# NET.net
KiCad netlist of a schematic drawn in Altium Designer
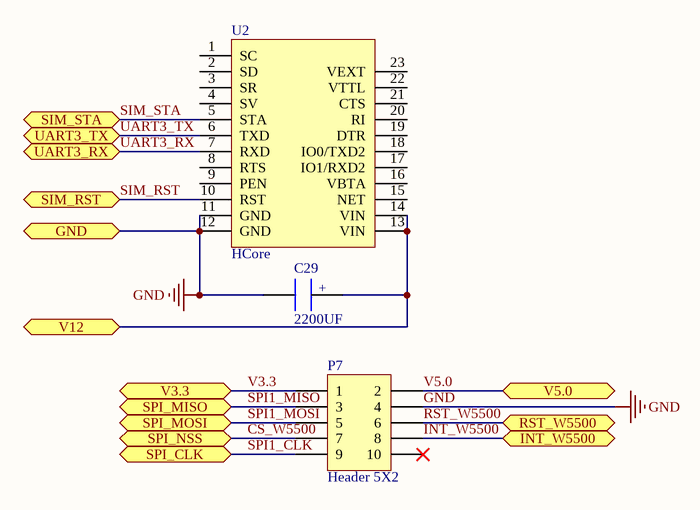
[diagram p0: NET.SchDoc]

(export (version "E")
  (design (tool "Eeschema 10.0.6"))
  (components
    (comp (ref "C29") (value "2200UF") (footprint "8X12_CAP") (libsource (lib "mylib") (part "CAP")))
    (comp (ref "P7")
      (value "Header 5X2")
      (footprint "HDR2X5")
      (description "Header, 5-Pin, Dual row")
      (fields (field (name "PUBLISHER") "Altium Limited"))
      (libsource (lib "Miscellaneous Connectors") (part "Header 5X2"))
    )
    (comp (ref "U2") (value "HCore") (footprint "HCore") (libsource (lib "mylib") (part "HCore")))
  )
  (nets
    (net (code "1") (name "/CS_W5500") (class "Default")
      (node (ref "P7") (pin "7") (pinfunction "7_7") (pintype "passive"))
    )
    (net (code "2") (name "/INT_W5500") (class "Default")
      (node (ref "P7") (pin "8") (pinfunction "8_8") (pintype "passive"))
    )
    (net (code "3") (name "/RST_W5500") (class "Default")
      (node (ref "P7") (pin "6") (pinfunction "6_6") (pintype "passive"))
    )
    (net (code "4") (name "/SIM_RST") (class "Default")
      (node (ref "U2") (pin "10") (pinfunction "RST_10") (pintype "passive"))
    )
    (net (code "5") (name "/SIM_STA") (class "Default")
      (node (ref "U2") (pin "5") (pinfunction "STA_5") (pintype "passive"))
    )
    (net (code "6") (name "/SPI1_CLK") (class "Default")
      (node (ref "P7") (pin "9") (pinfunction "9_9") (pintype "passive"))
    )
    (net (code "7") (name "/SPI1_MISO") (class "Default")
      (node (ref "P7") (pin "3") (pinfunction "3_3") (pintype "passive"))
    )
    (net (code "8") (name "/SPI1_MOSI") (class "Default")
      (node (ref "P7") (pin "5") (pinfunction "5_5") (pintype "passive"))
    )
    (net (code "9") (name "/UART3_RX") (class "Default")
      (node (ref "U2") (pin "7") (pinfunction "RXD_7") (pintype "passive"))
    )
    (net (code "10") (name "/UART3_TX") (class "Default")
      (node (ref "U2") (pin "6") (pinfunction "TXD_6") (pintype "passive"))
    )
    (net (code "11") (name "/V3.3") (class "Default")
      (node (ref "P7") (pin "1") (pinfunction "1_1") (pintype "passive"))
    )
    (net (code "12") (name "/V5.0") (class "Default")
      (node (ref "P7") (pin "2") (pinfunction "2_2") (pintype "passive"))
    )
    (net (code "13") (name "/V12") (class "Default")
      (node (ref "C29") (pin "1") (pinfunction "1_1") (pintype "passive"))
      (node (ref "U2") (pin "13") (pinfunction "VIN_13") (pintype "passive"))
      (node (ref "U2") (pin "14") (pinfunction "VIN_14") (pintype "passive"))
    )
    (net (code "14") (name "GND") (class "Default")
      (node (ref "C29") (pin "2") (pinfunction "2_2") (pintype "passive"))
      (node (ref "P7") (pin "4") (pinfunction "4_4") (pintype "passive"))
      (node (ref "U2") (pin "11") (pinfunction "GND_11") (pintype "passive"))
      (node (ref "U2") (pin "12") (pinfunction "GND_12") (pintype "passive"))
    )
    (net (code "15") (name "unconnected-(P7-Pad10)") (class "Default")
      (node (ref "P7") (pin "10") (pinfunction "10_10") (pintype "passive+no_connect"))
    )
    (net (code "16") (name "unconnected-(U2-CTS-Pad21)") (class "Default")
      (node (ref "U2") (pin "21") (pinfunction "CTS_21") (pintype "passive"))
    )
    (net (code "17") (name "unconnected-(U2-DTR-Pad19)") (class "Default")
      (node (ref "U2") (pin "19") (pinfunction "DTR_19") (pintype "passive"))
    )
    (net (code "18") (name "unconnected-(U2-IO0{slash}TXD2-Pad18)") (class "Default")
      (node (ref "U2") (pin "18") (pinfunction "IO0/TXD2_18") (pintype "passive"))
    )
    (net (code "19") (name "unconnected-(U2-IO1{slash}RXD2-Pad17)") (class "Default")
      (node (ref "U2") (pin "17") (pinfunction "IO1/RXD2_17") (pintype "passive"))
    )
    (net (code "20") (name "unconnected-(U2-NET-Pad15)") (class "Default")
      (node (ref "U2") (pin "15") (pinfunction "NET_15") (pintype "passive"))
    )
    (net (code "21") (name "unconnected-(U2-PEN-Pad9)") (class "Default")
      (node (ref "U2") (pin "9") (pinfunction "PEN_9") (pintype "passive"))
    )
    (net (code "22") (name "unconnected-(U2-RI-Pad20)") (class "Default")
      (node (ref "U2") (pin "20") (pinfunction "RI_20") (pintype "passive"))
    )
    (net (code "23") (name "unconnected-(U2-RTS-Pad8)") (class "Default")
      (node (ref "U2") (pin "8") (pinfunction "RTS_8") (pintype "passive"))
    )
    (net (code "24") (name "unconnected-(U2-SC-Pad1)") (class "Default")
      (node (ref "U2") (pin "1") (pinfunction "SC_1") (pintype "passive"))
    )
    (net (code "25") (name "unconnected-(U2-SD-Pad2)") (class "Default")
      (node (ref "U2") (pin "2") (pinfunction "SD_2") (pintype "passive"))
    )
    (net (code "26") (name "unconnected-(U2-SR-Pad3)") (class "Default")
      (node (ref "U2") (pin "3") (pinfunction "SR_3") (pintype "passive"))
    )
    (net (code "27") (name "unconnected-(U2-SV-Pad4)") (class "Default")
      (node (ref "U2") (pin "4") (pinfunction "SV_4") (pintype "passive"))
    )
    (net (code "28") (name "unconnected-(U2-VBTA-Pad16)") (class "Default")
      (node (ref "U2") (pin "16") (pinfunction "VBTA_16") (pintype "passive"))
    )
    (net (code "29") (name "unconnected-(U2-VEXT-Pad23)") (class "Default")
      (node (ref "U2") (pin "23") (pinfunction "VEXT_23") (pintype "passive"))
    )
    (net (code "30") (name "unconnected-(U2-VTTL-Pad22)") (class "Default")
      (node (ref "U2") (pin "22") (pinfunction "VTTL_22") (pintype "passive"))
    )
  )
)
